# vca.net
KiCad netlist of a schematic drawn in EAGLE
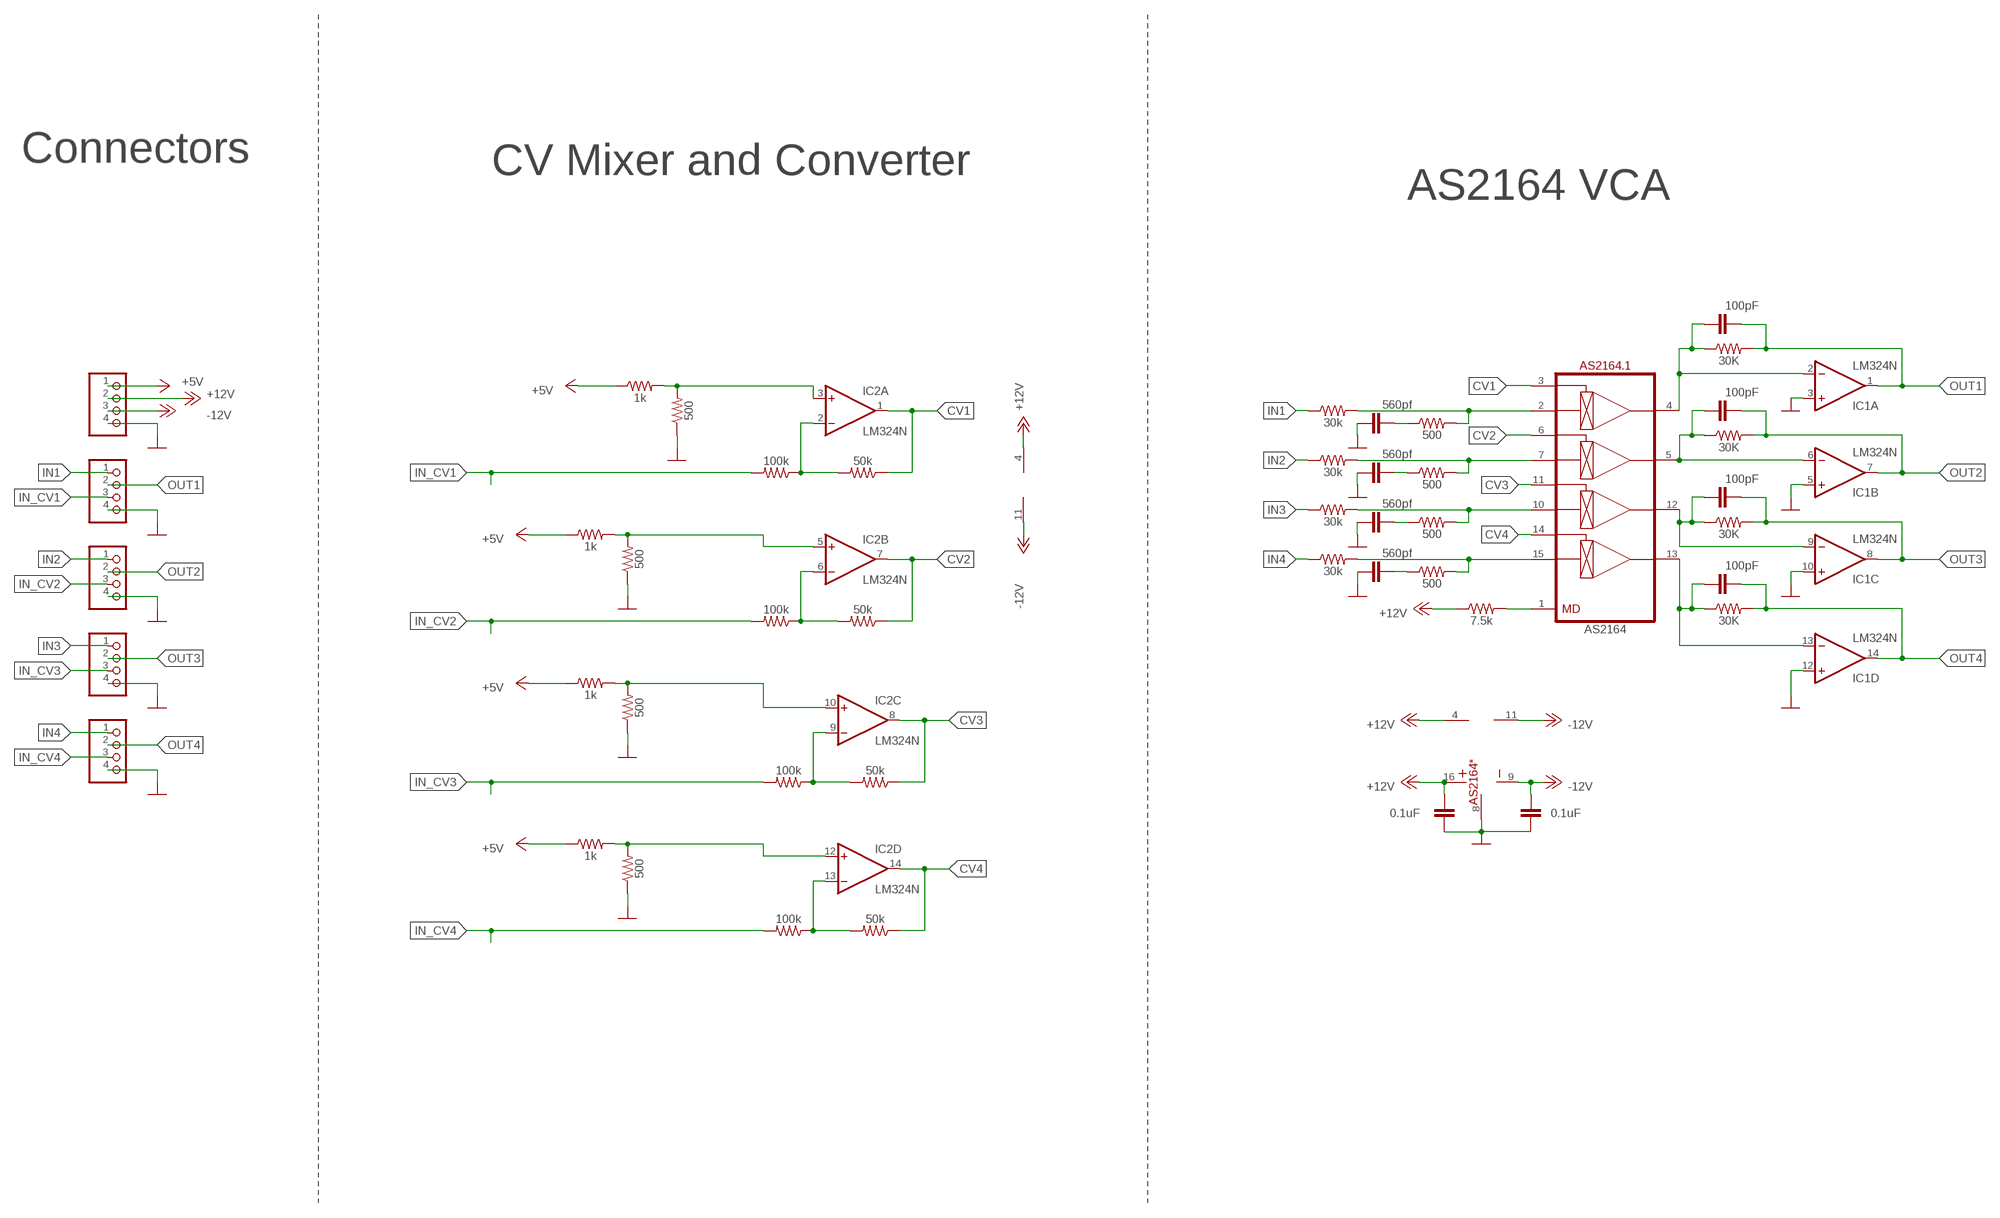
[diagram p0: schematic, sheet 1]

(export (version "E")
  (design (tool "Eeschema 10.0.6"))
  (components
    (comp (ref "AS2164")
      (value "AS2164")
      (footprint "eagle-import:DIP-16")
      (libsource (lib "eagle-import") (part "V2164D"))
    )
    (comp (ref "C1")
      (value "560pf")
      (footprint "eagle-import:CAP-PTH-SMALL-KIT")
      (libsource (lib "eagle-import") (part "0.1UF-KIT-EZ-50V-20%"))
    )
    (comp (ref "C2")
      (value "560pf")
      (footprint "eagle-import:CAP-PTH-SMALL-KIT")
      (libsource (lib "eagle-import") (part "0.1UF-KIT-EZ-50V-20%"))
    )
    (comp (ref "C3")
      (value "560pf")
      (footprint "eagle-import:CAP-PTH-SMALL-KIT")
      (libsource (lib "eagle-import") (part "0.1UF-KIT-EZ-50V-20%"))
    )
    (comp (ref "C4")
      (value "560pf")
      (footprint "eagle-import:CAP-PTH-SMALL-KIT")
      (libsource (lib "eagle-import") (part "0.1UF-KIT-EZ-50V-20%"))
    )
    (comp (ref "C5")
      (value "0.1uF")
      (footprint "eagle-import:CAP-PTH-SMALL-KIT")
      (libsource (lib "eagle-import") (part "0.1UF-KIT-EZ-50V-20%"))
    )
    (comp (ref "C6")
      (value "0.1uF")
      (footprint "eagle-import:CAP-PTH-SMALL-KIT")
      (libsource (lib "eagle-import") (part "0.1UF-KIT-EZ-50V-20%"))
    )
    (comp (ref "C7")
      (value "100pF")
      (footprint "eagle-import:CAP-PTH-SMALL-KIT")
      (libsource (lib "eagle-import") (part "0.1UF-KIT-EZ-50V-20%"))
    )
    (comp (ref "C8")
      (value "100pF")
      (footprint "eagle-import:CAP-PTH-SMALL-KIT")
      (libsource (lib "eagle-import") (part "0.1UF-KIT-EZ-50V-20%"))
    )
    (comp (ref "C9")
      (value "100pF")
      (footprint "eagle-import:CAP-PTH-SMALL-KIT")
      (libsource (lib "eagle-import") (part "0.1UF-KIT-EZ-50V-20%"))
    )
    (comp (ref "C10")
      (value "100pF")
      (footprint "eagle-import:CAP-PTH-SMALL-KIT")
      (libsource (lib "eagle-import") (part "0.1UF-KIT-EZ-50V-20%"))
    )
    (comp (ref "IC1")
      (value "LM324N")
      (footprint "eagle-import:DIL14")
      (libsource (lib "eagle-import") (part "LM324N"))
    )
    (comp (ref "IC2")
      (value "LM324N")
      (footprint "eagle-import:DIL14")
      (libsource (lib "eagle-import") (part "LM324N"))
    )
    (comp (ref "JP1")
      (value "PINHD-1X4")
      (footprint "eagle-import:1X04")
      (libsource (lib "eagle-import") (part "PINHD-1X4"))
    )
    (comp (ref "JP5")
      (value "PINHD-1X4")
      (footprint "eagle-import:1X04")
      (libsource (lib "eagle-import") (part "PINHD-1X4"))
    )
    (comp (ref "JP6")
      (value "PINHD-1X4")
      (footprint "eagle-import:1X04")
      (libsource (lib "eagle-import") (part "PINHD-1X4"))
    )
    (comp (ref "JP7")
      (value "PINHD-1X4")
      (footprint "eagle-import:1X04")
      (libsource (lib "eagle-import") (part "PINHD-1X4"))
    )
    (comp (ref "JP8")
      (value "PINHD-1X4")
      (footprint "eagle-import:1X04")
      (libsource (lib "eagle-import") (part "PINHD-1X4"))
    )
    (comp (ref "R1")
      (value "30k")
      (footprint "eagle-import:AXIAL-0.3")
      (libsource (lib "eagle-import") (part "RESISTORAXIAL-0.3"))
    )
    (comp (ref "R2")
      (value "30k")
      (footprint "eagle-import:AXIAL-0.3")
      (libsource (lib "eagle-import") (part "RESISTORAXIAL-0.3"))
    )
    (comp (ref "R3")
      (value "30k")
      (footprint "eagle-import:AXIAL-0.3")
      (libsource (lib "eagle-import") (part "RESISTORAXIAL-0.3"))
    )
    (comp (ref "R4")
      (value "500")
      (footprint "eagle-import:AXIAL-0.3")
      (libsource (lib "eagle-import") (part "RESISTORAXIAL-0.3"))
    )
    (comp (ref "R5")
      (value "30k")
      (footprint "eagle-import:AXIAL-0.3")
      (libsource (lib "eagle-import") (part "RESISTORAXIAL-0.3"))
    )
    (comp (ref "R6")
      (value "500")
      (footprint "eagle-import:AXIAL-0.3")
      (libsource (lib "eagle-import") (part "RESISTORAXIAL-0.3"))
    )
    (comp (ref "R7")
      (value "500")
      (footprint "eagle-import:AXIAL-0.3")
      (libsource (lib "eagle-import") (part "RESISTORAXIAL-0.3"))
    )
    (comp (ref "R8")
      (value "500")
      (footprint "eagle-import:AXIAL-0.3")
      (libsource (lib "eagle-import") (part "RESISTORAXIAL-0.3"))
    )
    (comp (ref "R9")
      (value "500")
      (footprint "eagle-import:AXIAL-0.3")
      (libsource (lib "eagle-import") (part "RESISTORAXIAL-0.3"))
    )
    (comp (ref "R10")
      (value "1k")
      (footprint "eagle-import:AXIAL-0.3")
      (libsource (lib "eagle-import") (part "RESISTORAXIAL-0.3"))
    )
    (comp (ref "R11")
      (value "100k")
      (footprint "eagle-import:AXIAL-0.3")
      (libsource (lib "eagle-import") (part "RESISTORAXIAL-0.3"))
    )
    (comp (ref "R12")
      (value "50k")
      (footprint "eagle-import:AXIAL-0.3")
      (libsource (lib "eagle-import") (part "RESISTORAXIAL-0.3"))
    )
    (comp (ref "R13")
      (value "1k")
      (footprint "eagle-import:AXIAL-0.3")
      (libsource (lib "eagle-import") (part "RESISTORAXIAL-0.3"))
    )
    (comp (ref "R14")
      (value "500")
      (footprint "eagle-import:AXIAL-0.3")
      (libsource (lib "eagle-import") (part "RESISTORAXIAL-0.3"))
    )
    (comp (ref "R15")
      (value "100k")
      (footprint "eagle-import:AXIAL-0.3")
      (libsource (lib "eagle-import") (part "RESISTORAXIAL-0.3"))
    )
    (comp (ref "R16")
      (value "50k")
      (footprint "eagle-import:AXIAL-0.3")
      (libsource (lib "eagle-import") (part "RESISTORAXIAL-0.3"))
    )
    (comp (ref "R17")
      (value "1k")
      (footprint "eagle-import:AXIAL-0.3")
      (libsource (lib "eagle-import") (part "RESISTORAXIAL-0.3"))
    )
    (comp (ref "R18")
      (value "500")
      (footprint "eagle-import:AXIAL-0.3")
      (libsource (lib "eagle-import") (part "RESISTORAXIAL-0.3"))
    )
    (comp (ref "R19")
      (value "100k")
      (footprint "eagle-import:AXIAL-0.3")
      (libsource (lib "eagle-import") (part "RESISTORAXIAL-0.3"))
    )
    (comp (ref "R20")
      (value "50k")
      (footprint "eagle-import:AXIAL-0.3")
      (libsource (lib "eagle-import") (part "RESISTORAXIAL-0.3"))
    )
    (comp (ref "R21")
      (value "1k")
      (footprint "eagle-import:AXIAL-0.3")
      (libsource (lib "eagle-import") (part "RESISTORAXIAL-0.3"))
    )
    (comp (ref "R22")
      (value "500")
      (footprint "eagle-import:AXIAL-0.3")
      (libsource (lib "eagle-import") (part "RESISTORAXIAL-0.3"))
    )
    (comp (ref "R23")
      (value "100k")
      (footprint "eagle-import:AXIAL-0.3")
      (libsource (lib "eagle-import") (part "RESISTORAXIAL-0.3"))
    )
    (comp (ref "R24")
      (value "50k")
      (footprint "eagle-import:AXIAL-0.3")
      (libsource (lib "eagle-import") (part "RESISTORAXIAL-0.3"))
    )
    (comp (ref "R25")
      (value "7.5k")
      (footprint "eagle-import:AXIAL-0.3")
      (libsource (lib "eagle-import") (part "RESISTORAXIAL-0.3"))
    )
    (comp (ref "R26")
      (value "30K")
      (footprint "eagle-import:AXIAL-0.3")
      (libsource (lib "eagle-import") (part "RESISTORAXIAL-0.3"))
    )
    (comp (ref "R27")
      (value "30K")
      (footprint "eagle-import:AXIAL-0.3")
      (libsource (lib "eagle-import") (part "RESISTORAXIAL-0.3"))
    )
    (comp (ref "R28")
      (value "30K")
      (footprint "eagle-import:AXIAL-0.3")
      (libsource (lib "eagle-import") (part "RESISTORAXIAL-0.3"))
    )
    (comp (ref "R29")
      (value "30K")
      (footprint "eagle-import:AXIAL-0.3")
      (libsource (lib "eagle-import") (part "RESISTORAXIAL-0.3"))
    )
  )
  (nets
    (net (code "1") (name "+5V") (class "Default")
      (node (ref "JP6") (pin "1") (pinfunction "1_1") (pintype "passive"))
      (node (ref "R10") (pin "P$1") (pinfunction "1_P$1") (pintype "passive"))
      (node (ref "R13") (pin "P$1") (pinfunction "1_P$1") (pintype "passive"))
      (node (ref "R17") (pin "P$1") (pinfunction "1_P$1") (pintype "passive"))
      (node (ref "R21") (pin "P$1") (pinfunction "1_P$1") (pintype "passive"))
    )
    (net (code "2") (name "+12V") (class "Default")
      (node (ref "AS2164") (pin "16") (pinfunction "V+_16") (pintype "power_in"))
      (node (ref "C5") (pin "2") (pinfunction "2_2") (pintype "passive"))
      (node (ref "IC1") (pin "4") (pinfunction "V+_4") (pintype "power_in"))
      (node (ref "IC2") (pin "4") (pinfunction "V+_4") (pintype "power_in"))
      (node (ref "JP6") (pin "2") (pinfunction "2_2") (pintype "passive"))
      (node (ref "R25") (pin "P$1") (pinfunction "1_P$1") (pintype "passive"))
    )
    (net (code "3") (name "-12V") (class "Default")
      (node (ref "AS2164") (pin "9") (pinfunction "V-_9") (pintype "power_in"))
      (node (ref "C6") (pin "2") (pinfunction "2_2") (pintype "passive"))
      (node (ref "IC1") (pin "11") (pinfunction "V-_11") (pintype "power_in"))
      (node (ref "IC2") (pin "11") (pinfunction "V-_11") (pintype "power_in"))
      (node (ref "JP6") (pin "3") (pinfunction "3_3") (pintype "passive"))
    )
    (net (code "4") (name "CV1") (class "Default")
      (node (ref "AS2164") (pin "3") (pinfunction "CV1_3") (pintype "input"))
      (node (ref "IC2") (pin "1") (pinfunction "OUT_1") (pintype "output"))
      (node (ref "R20") (pin "P$1") (pinfunction "1_P$1") (pintype "passive"))
    )
    (net (code "5") (name "CV2") (class "Default")
      (node (ref "AS2164") (pin "6") (pinfunction "CV2_6") (pintype "input"))
      (node (ref "IC2") (pin "7") (pinfunction "OUT_7") (pintype "output"))
      (node (ref "R16") (pin "P$1") (pinfunction "1_P$1") (pintype "passive"))
    )
    (net (code "6") (name "CV3") (class "Default")
      (node (ref "AS2164") (pin "11") (pinfunction "CV3_11") (pintype "input"))
      (node (ref "IC2") (pin "8") (pinfunction "OUT_8") (pintype "output"))
      (node (ref "R12") (pin "P$1") (pinfunction "1_P$1") (pintype "passive"))
    )
    (net (code "7") (name "CV4") (class "Default")
      (node (ref "AS2164") (pin "14") (pinfunction "CV4_14") (pintype "input"))
      (node (ref "IC2") (pin "14") (pinfunction "OUT_14") (pintype "output"))
      (node (ref "R24") (pin "P$1") (pinfunction "1_P$1") (pintype "passive"))
    )
    (net (code "8") (name "GND") (class "Default")
      (node (ref "AS2164") (pin "8") (pinfunction "GND_8") (pintype "power_in"))
      (node (ref "C1") (pin "1") (pinfunction "1_1") (pintype "passive"))
      (node (ref "C2") (pin "1") (pinfunction "1_1") (pintype "passive"))
      (node (ref "C3") (pin "1") (pinfunction "1_1") (pintype "passive"))
      (node (ref "C4") (pin "1") (pinfunction "1_1") (pintype "passive"))
      (node (ref "C5") (pin "1") (pinfunction "1_1") (pintype "passive"))
      (node (ref "C6") (pin "1") (pinfunction "1_1") (pintype "passive"))
      (node (ref "IC1") (pin "10") (pinfunction "+IN_10") (pintype "input"))
      (node (ref "IC1") (pin "12") (pinfunction "+IN_12") (pintype "input"))
      (node (ref "IC1") (pin "3") (pinfunction "+IN_3") (pintype "input"))
      (node (ref "IC1") (pin "5") (pinfunction "+IN_5") (pintype "input"))
      (node (ref "JP1") (pin "4") (pinfunction "4_4") (pintype "passive"))
      (node (ref "JP5") (pin "4") (pinfunction "4_4") (pintype "passive"))
      (node (ref "JP6") (pin "4") (pinfunction "4_4") (pintype "passive"))
      (node (ref "JP7") (pin "4") (pinfunction "4_4") (pintype "passive"))
      (node (ref "JP8") (pin "4") (pinfunction "4_4") (pintype "passive"))
      (node (ref "R14") (pin "P$1") (pinfunction "1_P$1") (pintype "passive"))
      (node (ref "R18") (pin "P$1") (pinfunction "1_P$1") (pintype "passive"))
      (node (ref "R22") (pin "P$1") (pinfunction "1_P$1") (pintype "passive"))
      (node (ref "R9") (pin "P$1") (pinfunction "1_P$1") (pintype "passive"))
    )
    (net (code "9") (name "IN1") (class "Default")
      (node (ref "JP5") (pin "1") (pinfunction "1_1") (pintype "passive"))
      (node (ref "R1") (pin "P$1") (pinfunction "1_P$1") (pintype "passive"))
    )
    (net (code "10") (name "IN2") (class "Default")
      (node (ref "JP7") (pin "1") (pinfunction "1_1") (pintype "passive"))
      (node (ref "R2") (pin "P$1") (pinfunction "1_P$1") (pintype "passive"))
    )
    (net (code "11") (name "IN3") (class "Default")
      (node (ref "JP1") (pin "1") (pinfunction "1_1") (pintype "passive"))
      (node (ref "R3") (pin "P$1") (pinfunction "1_P$1") (pintype "passive"))
    )
    (net (code "12") (name "IN4") (class "Default")
      (node (ref "JP8") (pin "1") (pinfunction "1_1") (pintype "passive"))
      (node (ref "R5") (pin "P$1") (pinfunction "1_P$1") (pintype "passive"))
    )
    (net (code "13") (name "IN_CV1") (class "Default")
      (node (ref "JP5") (pin "3") (pinfunction "3_3") (pintype "passive"))
      (node (ref "R19") (pin "P$2") (pinfunction "2_P$2") (pintype "passive"))
    )
    (net (code "14") (name "IN_CV2") (class "Default")
      (node (ref "JP7") (pin "3") (pinfunction "3_3") (pintype "passive"))
      (node (ref "R15") (pin "P$2") (pinfunction "2_P$2") (pintype "passive"))
    )
    (net (code "15") (name "IN_CV3") (class "Default")
      (node (ref "JP1") (pin "3") (pinfunction "3_3") (pintype "passive"))
      (node (ref "R11") (pin "P$2") (pinfunction "2_P$2") (pintype "passive"))
    )
    (net (code "16") (name "IN_CV4") (class "Default")
      (node (ref "JP8") (pin "3") (pinfunction "3_3") (pintype "passive"))
      (node (ref "R23") (pin "P$2") (pinfunction "2_P$2") (pintype "passive"))
    )
    (net (code "17") (name "Net-(AS2164B-IN1)") (class "Default")
      (node (ref "AS2164") (pin "2") (pinfunction "IN1_2") (pintype "input"))
      (node (ref "R1") (pin "P$2") (pinfunction "2_P$2") (pintype "passive"))
      (node (ref "R8") (pin "P$2") (pinfunction "2_P$2") (pintype "passive"))
    )
    (net (code "18") (name "Net-(AS2164B-IN2)") (class "Default")
      (node (ref "AS2164") (pin "7") (pinfunction "IN2_7") (pintype "input"))
      (node (ref "R2") (pin "P$2") (pinfunction "2_P$2") (pintype "passive"))
      (node (ref "R7") (pin "P$2") (pinfunction "2_P$2") (pintype "passive"))
    )
    (net (code "19") (name "Net-(AS2164B-IN3)") (class "Default")
      (node (ref "AS2164") (pin "10") (pinfunction "IN3_10") (pintype "input"))
      (node (ref "R3") (pin "P$2") (pinfunction "2_P$2") (pintype "passive"))
      (node (ref "R6") (pin "P$2") (pinfunction "2_P$2") (pintype "passive"))
    )
    (net (code "20") (name "Net-(AS2164B-IN4)") (class "Default")
      (node (ref "AS2164") (pin "15") (pinfunction "IN4_15") (pintype "input"))
      (node (ref "R4") (pin "P$2") (pinfunction "2_P$2") (pintype "passive"))
      (node (ref "R5") (pin "P$2") (pinfunction "2_P$2") (pintype "passive"))
    )
    (net (code "21") (name "Net-(AS2164B-MD)") (class "Default")
      (node (ref "AS2164") (pin "1") (pinfunction "MD_1") (pintype "output"))
      (node (ref "R25") (pin "P$2") (pinfunction "2_P$2") (pintype "passive"))
    )
    (net (code "22") (name "Net-(AS2164B-OUT1)") (class "Default")
      (node (ref "AS2164") (pin "4") (pinfunction "OUT1_4") (pintype "output"))
      (node (ref "C10") (pin "1") (pinfunction "1_1") (pintype "passive"))
      (node (ref "IC1") (pin "2") (pinfunction "-IN_2") (pintype "input"))
      (node (ref "R29") (pin "P$1") (pinfunction "1_P$1") (pintype "passive"))
    )
    (net (code "23") (name "Net-(AS2164B-OUT2)") (class "Default")
      (node (ref "AS2164") (pin "5") (pinfunction "OUT2_5") (pintype "output"))
      (node (ref "C9") (pin "1") (pinfunction "1_1") (pintype "passive"))
      (node (ref "IC1") (pin "6") (pinfunction "-IN_6") (pintype "input"))
      (node (ref "R28") (pin "P$1") (pinfunction "1_P$1") (pintype "passive"))
    )
    (net (code "24") (name "Net-(AS2164B-OUT3)") (class "Default")
      (node (ref "AS2164") (pin "12") (pinfunction "OUT3_12") (pintype "output"))
      (node (ref "C8") (pin "1") (pinfunction "1_1") (pintype "passive"))
      (node (ref "IC1") (pin "9") (pinfunction "-IN_9") (pintype "input"))
      (node (ref "R27") (pin "P$1") (pinfunction "1_P$1") (pintype "passive"))
    )
    (net (code "25") (name "Net-(AS2164B-OUT4)") (class "Default")
      (node (ref "AS2164") (pin "13") (pinfunction "OUT4_13") (pintype "output"))
      (node (ref "C7") (pin "1") (pinfunction "1_1") (pintype "passive"))
      (node (ref "IC1") (pin "13") (pinfunction "-IN_13") (pintype "input"))
      (node (ref "R26") (pin "P$1") (pinfunction "1_P$1") (pintype "passive"))
    )
    (net (code "26") (name "Net-(IC2A-+IN)") (class "Default")
      (node (ref "IC2") (pin "3") (pinfunction "+IN_3") (pintype "input"))
      (node (ref "R10") (pin "P$2") (pinfunction "2_P$2") (pintype "passive"))
      (node (ref "R9") (pin "P$2") (pinfunction "2_P$2") (pintype "passive"))
    )
    (net (code "27") (name "Net-(IC2A--IN)") (class "Default")
      (node (ref "IC2") (pin "2") (pinfunction "-IN_2") (pintype "input"))
      (node (ref "R19") (pin "P$1") (pinfunction "1_P$1") (pintype "passive"))
      (node (ref "R20") (pin "P$2") (pinfunction "2_P$2") (pintype "passive"))
    )
    (net (code "28") (name "Net-(IC2B-+IN)") (class "Default")
      (node (ref "IC2") (pin "5") (pinfunction "+IN_5") (pintype "input"))
      (node (ref "R13") (pin "P$2") (pinfunction "2_P$2") (pintype "passive"))
      (node (ref "R14") (pin "P$2") (pinfunction "2_P$2") (pintype "passive"))
    )
    (net (code "29") (name "Net-(IC2B--IN)") (class "Default")
      (node (ref "IC2") (pin "6") (pinfunction "-IN_6") (pintype "input"))
      (node (ref "R15") (pin "P$1") (pinfunction "1_P$1") (pintype "passive"))
      (node (ref "R16") (pin "P$2") (pinfunction "2_P$2") (pintype "passive"))
    )
    (net (code "30") (name "Net-(IC2C-+IN)") (class "Default")
      (node (ref "IC2") (pin "10") (pinfunction "+IN_10") (pintype "input"))
      (node (ref "R17") (pin "P$2") (pinfunction "2_P$2") (pintype "passive"))
      (node (ref "R18") (pin "P$2") (pinfunction "2_P$2") (pintype "passive"))
    )
    (net (code "31") (name "Net-(IC2C--IN)") (class "Default")
      (node (ref "IC2") (pin "9") (pinfunction "-IN_9") (pintype "input"))
      (node (ref "R11") (pin "P$1") (pinfunction "1_P$1") (pintype "passive"))
      (node (ref "R12") (pin "P$2") (pinfunction "2_P$2") (pintype "passive"))
    )
    (net (code "32") (name "Net-(IC2D-+IN)") (class "Default")
      (node (ref "IC2") (pin "12") (pinfunction "+IN_12") (pintype "input"))
      (node (ref "R21") (pin "P$2") (pinfunction "2_P$2") (pintype "passive"))
      (node (ref "R22") (pin "P$2") (pinfunction "2_P$2") (pintype "passive"))
    )
    (net (code "33") (name "Net-(IC2D--IN)") (class "Default")
      (node (ref "IC2") (pin "13") (pinfunction "-IN_13") (pintype "input"))
      (node (ref "R23") (pin "P$1") (pinfunction "1_P$1") (pintype "passive"))
      (node (ref "R24") (pin "P$2") (pinfunction "2_P$2") (pintype "passive"))
    )
    (net (code "34") (name "Net-(R4-1)") (class "Default")
      (node (ref "C4") (pin "2") (pinfunction "2_2") (pintype "passive"))
      (node (ref "R4") (pin "P$1") (pinfunction "1_P$1") (pintype "passive"))
    )
    (net (code "35") (name "Net-(R6-1)") (class "Default")
      (node (ref "C3") (pin "2") (pinfunction "2_2") (pintype "passive"))
      (node (ref "R6") (pin "P$1") (pinfunction "1_P$1") (pintype "passive"))
    )
    (net (code "36") (name "Net-(R7-1)") (class "Default")
      (node (ref "C2") (pin "2") (pinfunction "2_2") (pintype "passive"))
      (node (ref "R7") (pin "P$1") (pinfunction "1_P$1") (pintype "passive"))
    )
    (net (code "37") (name "Net-(R8-1)") (class "Default")
      (node (ref "C1") (pin "2") (pinfunction "2_2") (pintype "passive"))
      (node (ref "R8") (pin "P$1") (pinfunction "1_P$1") (pintype "passive"))
    )
    (net (code "38") (name "OUT1") (class "Default")
      (node (ref "C10") (pin "2") (pinfunction "2_2") (pintype "passive"))
      (node (ref "IC1") (pin "1") (pinfunction "OUT_1") (pintype "output"))
      (node (ref "JP5") (pin "2") (pinfunction "2_2") (pintype "passive"))
      (node (ref "R29") (pin "P$2") (pinfunction "2_P$2") (pintype "passive"))
    )
    (net (code "39") (name "OUT2") (class "Default")
      (node (ref "C9") (pin "2") (pinfunction "2_2") (pintype "passive"))
      (node (ref "IC1") (pin "7") (pinfunction "OUT_7") (pintype "output"))
      (node (ref "JP7") (pin "2") (pinfunction "2_2") (pintype "passive"))
      (node (ref "R28") (pin "P$2") (pinfunction "2_P$2") (pintype "passive"))
    )
    (net (code "40") (name "OUT3") (class "Default")
      (node (ref "C8") (pin "2") (pinfunction "2_2") (pintype "passive"))
      (node (ref "IC1") (pin "8") (pinfunction "OUT_8") (pintype "output"))
      (node (ref "JP1") (pin "2") (pinfunction "2_2") (pintype "passive"))
      (node (ref "R27") (pin "P$2") (pinfunction "2_P$2") (pintype "passive"))
    )
    (net (code "41") (name "OUT4") (class "Default")
      (node (ref "C7") (pin "2") (pinfunction "2_2") (pintype "passive"))
      (node (ref "IC1") (pin "14") (pinfunction "OUT_14") (pintype "output"))
      (node (ref "JP8") (pin "2") (pinfunction "2_2") (pintype "passive"))
      (node (ref "R26") (pin "P$2") (pinfunction "2_P$2") (pintype "passive"))
    )
  )
)
